# Micromouse_controller_v009.net
KiCad netlist of a schematic drawn in EAGLE
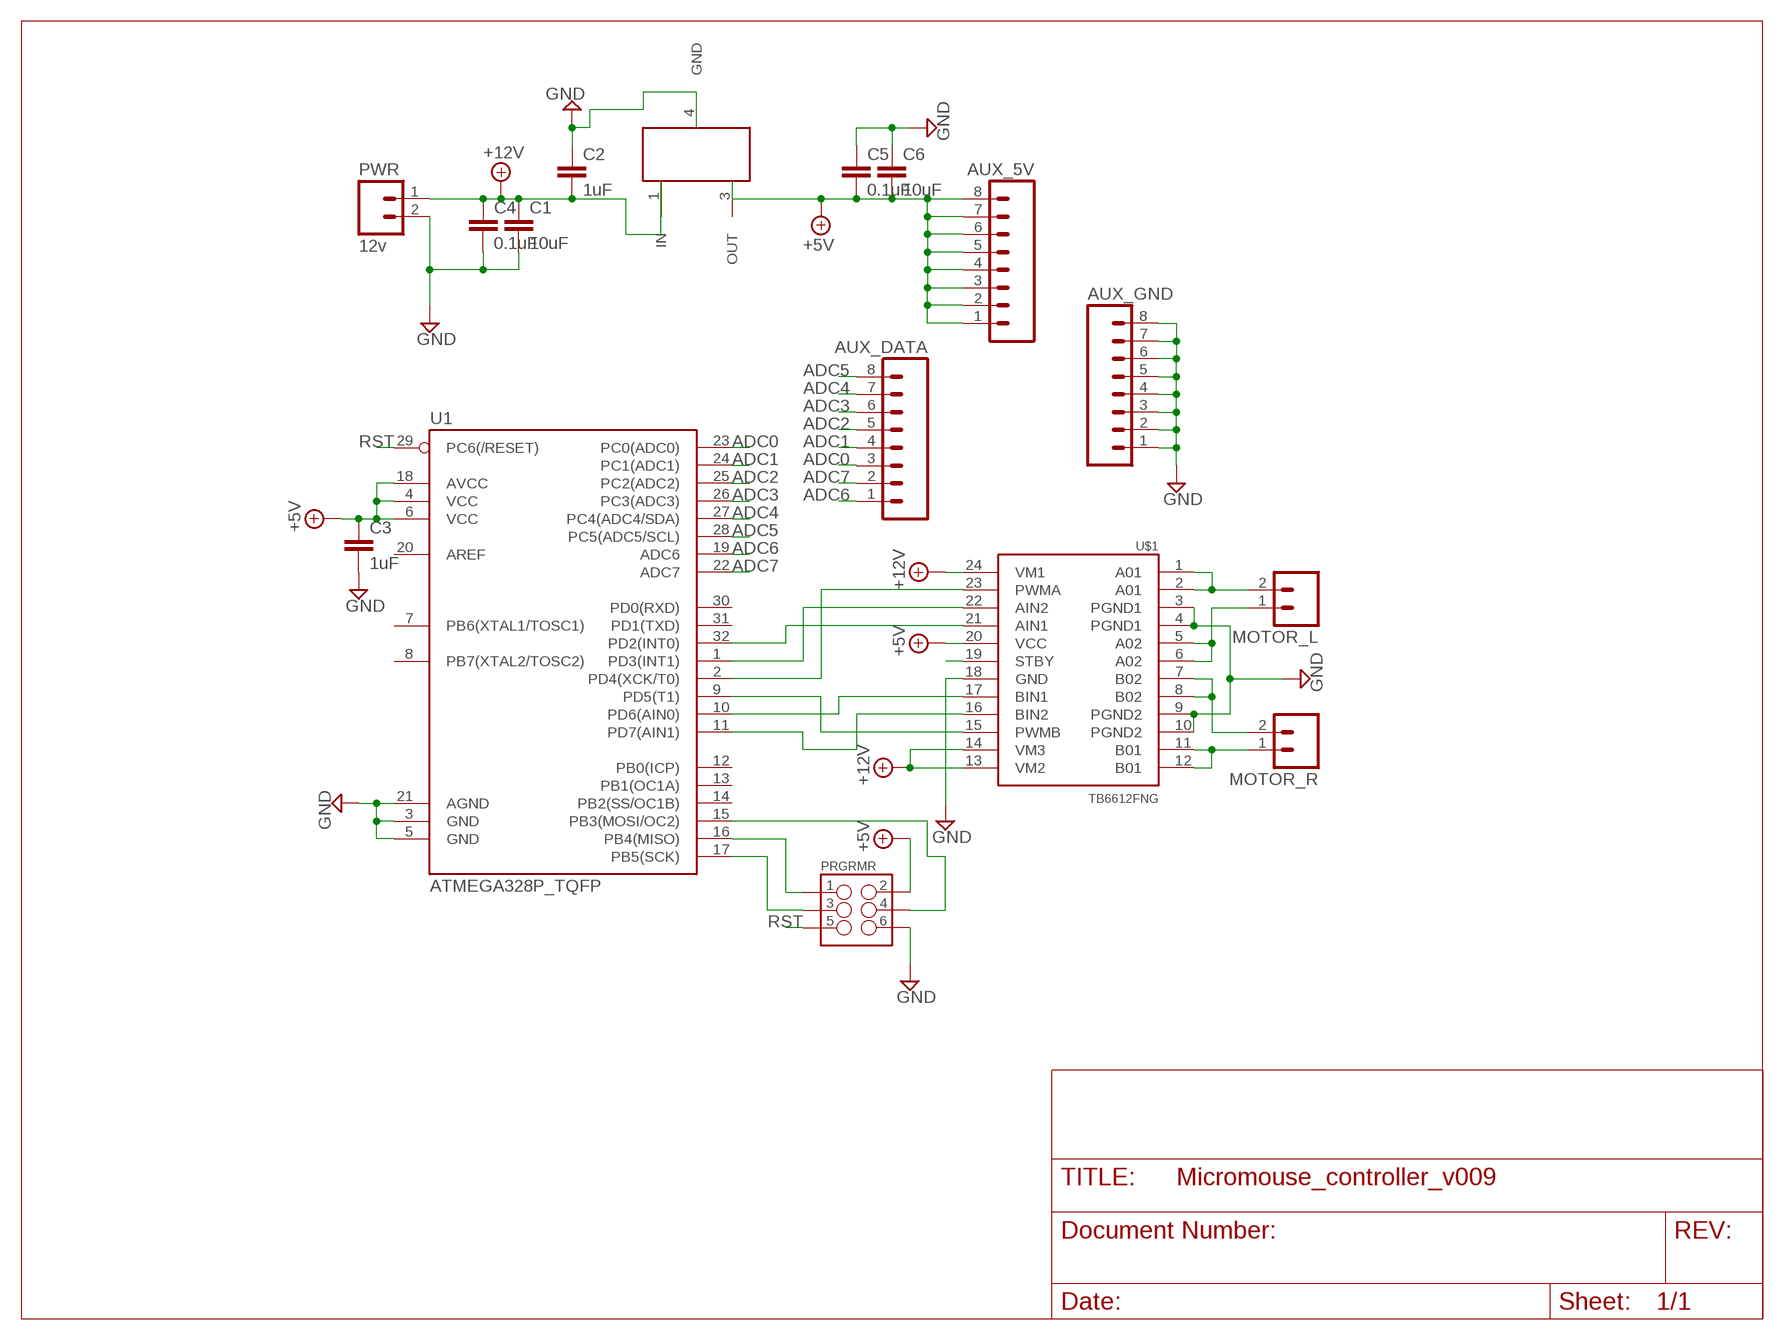
[diagram p0: schematic, sheet 1]

(export (version "E")
  (design (tool "Eeschema 10.0.6"))
  (components
    (comp (ref "AUX_5V")
      (value "M08SMD-STRAIGHT-ALT-FEMALE")
      (footprint "eagle-import:1X08_SMD_ALT")
      (libsource (lib "eagle-import") (part "M08SMD-STRAIGHT-ALT-FEMALE"))
    )
    (comp (ref "AUX_DATA")
      (value "M08SMD-STRAIGHT-ALT-FEMALE")
      (footprint "eagle-import:1X08_SMD_ALT")
      (libsource (lib "eagle-import") (part "M08SMD-STRAIGHT-ALT-FEMALE"))
    )
    (comp (ref "AUX_GND")
      (value "M08SMD-STRAIGHT-ALT-FEMALE")
      (footprint "eagle-import:1X08_SMD_ALT")
      (libsource (lib "eagle-import") (part "M08SMD-STRAIGHT-ALT-FEMALE"))
    )
    (comp (ref "C1")
      (value "10uF")
      (footprint "eagle-import:GRM43D")
      (libsource (lib "eagle-import") (part "CAPSMD"))
    )
    (comp (ref "C2")
      (value "1uF")
      (footprint "eagle-import:GRM43D")
      (libsource (lib "eagle-import") (part "CAPSMD"))
    )
    (comp (ref "C3")
      (value "1uF")
      (footprint "eagle-import:GRM43D")
      (libsource (lib "eagle-import") (part "CAPSMD"))
    )
    (comp (ref "C4")
      (value "0.1uF")
      (footprint "eagle-import:GRM43D")
      (libsource (lib "eagle-import") (part "CAPSMD"))
    )
    (comp (ref "C5")
      (value "0.1uF")
      (footprint "eagle-import:GRM43D")
      (libsource (lib "eagle-import") (part "CAPSMD"))
    )
    (comp (ref "C6")
      (value "10uF")
      (footprint "eagle-import:GRM43D")
      (libsource (lib "eagle-import") (part "CAPSMD"))
    )
    (comp (ref "IC2")
      (value "TA4805BF")
      (footprint "eagle-import:DPAK")
      (libsource (lib "eagle-import") (part "TA4805BF"))
    )
    (comp (ref "MOTOR_L")
      (value "M02-JST-2MM-SMT")
      (footprint "eagle-import:JST-2-SMD")
      (libsource (lib "eagle-import") (part "M02-JST-2MM-SMT"))
    )
    (comp (ref "MOTOR_R")
      (value "M02-JST-2MM-SMT")
      (footprint "eagle-import:JST-2-SMD")
      (libsource (lib "eagle-import") (part "M02-JST-2MM-SMT"))
    )
    (comp (ref "PRGRMR")
      (value "M03X2FEMALE_SMD")
      (footprint "eagle-import:2X3_SMD")
      (libsource (lib "eagle-import") (part "M03X2FEMALE_SMD"))
    )
    (comp (ref "PWR")
      (value "12v")
      (footprint "eagle-import:JST-2-SMD")
      (libsource (lib "eagle-import") (part "M02-JST-2MM-SMT"))
    )
    (comp (ref "U$1")
      (value "TB6612FNG")
      (footprint "eagle-import:SSOP24")
      (libsource (lib "eagle-import") (part "TB6612FNG"))
    )
    (comp (ref "U1")
      (value "ATMEGA328P_TQFP")
      (footprint "eagle-import:TQFP32-08")
      (libsource (lib "eagle-import") (part "ATMEGA328P_TQFP"))
    )
  )
  (nets
    (net (code "1") (name "+5V") (class "Default")
      (node (ref "AUX_5V") (pin "1") (pinfunction "1_1") (pintype "passive"))
      (node (ref "AUX_5V") (pin "2") (pinfunction "2_2") (pintype "passive"))
      (node (ref "AUX_5V") (pin "3") (pinfunction "3_3") (pintype "passive"))
      (node (ref "AUX_5V") (pin "4") (pinfunction "4_4") (pintype "passive"))
      (node (ref "AUX_5V") (pin "5") (pinfunction "5_5") (pintype "passive"))
      (node (ref "AUX_5V") (pin "6") (pinfunction "6_6") (pintype "passive"))
      (node (ref "AUX_5V") (pin "7") (pinfunction "7_7") (pintype "passive"))
      (node (ref "AUX_5V") (pin "8") (pinfunction "8_8") (pintype "passive"))
      (node (ref "C3") (pin "A") (pinfunction "1_A") (pintype "passive"))
      (node (ref "C5") (pin "C") (pinfunction "2_C") (pintype "passive"))
      (node (ref "C6") (pin "C") (pinfunction "2_C") (pintype "passive"))
      (node (ref "IC2") (pin "3") (pinfunction "OUT_3") (pintype "bidirectional"))
      (node (ref "PRGRMR") (pin "2") (pinfunction "2_2") (pintype "bidirectional"))
      (node (ref "U$1") (pin "20") (pinfunction "VCC_20") (pintype "bidirectional"))
      (node (ref "U1") (pin "18") (pinfunction "AVCC_18") (pintype "bidirectional"))
      (node (ref "U1") (pin "4") (pinfunction "VCC_4") (pintype "bidirectional"))
      (node (ref "U1") (pin "6") (pinfunction "VCC_6") (pintype "bidirectional"))
    )
    (net (code "2") (name "+12V") (class "Default")
      (node (ref "C1") (pin "A") (pinfunction "1_A") (pintype "passive"))
      (node (ref "C2") (pin "C") (pinfunction "2_C") (pintype "passive"))
      (node (ref "C4") (pin "A") (pinfunction "1_A") (pintype "passive"))
      (node (ref "IC2") (pin "1") (pinfunction "IN_1") (pintype "bidirectional"))
      (node (ref "PWR") (pin "1") (pinfunction "2_1") (pintype "passive"))
      (node (ref "U$1") (pin "13") (pinfunction "VM2_13") (pintype "bidirectional"))
      (node (ref "U$1") (pin "14") (pinfunction "VM3_14") (pintype "bidirectional"))
      (node (ref "U$1") (pin "24") (pinfunction "VM1_24") (pintype "bidirectional"))
    )
    (net (code "3") (name "/ADC0") (class "Default")
      (node (ref "AUX_DATA") (pin "3") (pinfunction "3_3") (pintype "passive"))
      (node (ref "U1") (pin "23") (pinfunction "PC0(ADC0)_23") (pintype "bidirectional"))
    )
    (net (code "4") (name "/ADC1") (class "Default")
      (node (ref "AUX_DATA") (pin "4") (pinfunction "4_4") (pintype "passive"))
      (node (ref "U1") (pin "24") (pinfunction "PC1(ADC1)_24") (pintype "bidirectional"))
    )
    (net (code "5") (name "/ADC2") (class "Default")
      (node (ref "AUX_DATA") (pin "5") (pinfunction "5_5") (pintype "passive"))
      (node (ref "U1") (pin "25") (pinfunction "PC2(ADC2)_25") (pintype "bidirectional"))
    )
    (net (code "6") (name "/ADC3") (class "Default")
      (node (ref "AUX_DATA") (pin "6") (pinfunction "6_6") (pintype "passive"))
      (node (ref "U1") (pin "26") (pinfunction "PC3(ADC3)_26") (pintype "bidirectional"))
    )
    (net (code "7") (name "/ADC4") (class "Default")
      (node (ref "AUX_DATA") (pin "7") (pinfunction "7_7") (pintype "passive"))
      (node (ref "U1") (pin "27") (pinfunction "PC4(ADC4/SDA)_27") (pintype "bidirectional"))
    )
    (net (code "8") (name "/ADC5") (class "Default")
      (node (ref "AUX_DATA") (pin "8") (pinfunction "8_8") (pintype "passive"))
      (node (ref "U1") (pin "28") (pinfunction "PC5(ADC5/SCL)_28") (pintype "bidirectional"))
    )
    (net (code "9") (name "/ADC6") (class "Default")
      (node (ref "AUX_DATA") (pin "1") (pinfunction "1_1") (pintype "passive"))
      (node (ref "U1") (pin "19") (pinfunction "ADC6_19") (pintype "bidirectional"))
    )
    (net (code "10") (name "/ADC7") (class "Default")
      (node (ref "AUX_DATA") (pin "2") (pinfunction "2_2") (pintype "passive"))
      (node (ref "U1") (pin "22") (pinfunction "ADC7_22") (pintype "bidirectional"))
    )
    (net (code "11") (name "/RST") (class "Default")
      (node (ref "PRGRMR") (pin "5") (pinfunction "5_5") (pintype "bidirectional"))
      (node (ref "U1") (pin "29") (pinfunction "PC6(/RESET)_29") (pintype "bidirectional"))
    )
    (net (code "12") (name "GND") (class "Default")
      (node (ref "AUX_GND") (pin "1") (pinfunction "1_1") (pintype "passive"))
      (node (ref "AUX_GND") (pin "2") (pinfunction "2_2") (pintype "passive"))
      (node (ref "AUX_GND") (pin "3") (pinfunction "3_3") (pintype "passive"))
      (node (ref "AUX_GND") (pin "4") (pinfunction "4_4") (pintype "passive"))
      (node (ref "AUX_GND") (pin "5") (pinfunction "5_5") (pintype "passive"))
      (node (ref "AUX_GND") (pin "6") (pinfunction "6_6") (pintype "passive"))
      (node (ref "AUX_GND") (pin "7") (pinfunction "7_7") (pintype "passive"))
      (node (ref "AUX_GND") (pin "8") (pinfunction "8_8") (pintype "passive"))
      (node (ref "C1") (pin "C") (pinfunction "2_C") (pintype "passive"))
      (node (ref "C2") (pin "A") (pinfunction "1_A") (pintype "passive"))
      (node (ref "C3") (pin "C") (pinfunction "2_C") (pintype "passive"))
      (node (ref "C4") (pin "C") (pinfunction "2_C") (pintype "passive"))
      (node (ref "C5") (pin "A") (pinfunction "1_A") (pintype "passive"))
      (node (ref "C6") (pin "A") (pinfunction "1_A") (pintype "passive"))
      (node (ref "IC2") (pin "4") (pinfunction "GND_4") (pintype "bidirectional"))
      (node (ref "PRGRMR") (pin "6") (pinfunction "6_6") (pintype "bidirectional"))
      (node (ref "PWR") (pin "2") (pinfunction "1_2") (pintype "passive"))
      (node (ref "U$1") (pin "10") (pinfunction "PGND2_10") (pintype "bidirectional"))
      (node (ref "U$1") (pin "18") (pinfunction "GND_18") (pintype "bidirectional"))
      (node (ref "U$1") (pin "3") (pinfunction "PGND1_3") (pintype "bidirectional"))
      (node (ref "U$1") (pin "4") (pinfunction "PGND1_4") (pintype "bidirectional"))
      (node (ref "U$1") (pin "9") (pinfunction "PGND2_9") (pintype "bidirectional"))
      (node (ref "U1") (pin "21") (pinfunction "AGND_21") (pintype "bidirectional"))
      (node (ref "U1") (pin "3") (pinfunction "GND_3") (pintype "bidirectional"))
      (node (ref "U1") (pin "5") (pinfunction "GND_5") (pintype "bidirectional"))
    )
    (net (code "13") (name "Net-(MOTOR_L-1)") (class "Default")
      (node (ref "MOTOR_L") (pin "2") (pinfunction "1_2") (pintype "passive"))
      (node (ref "U$1") (pin "1") (pinfunction "A01_1") (pintype "bidirectional"))
      (node (ref "U$1") (pin "2") (pinfunction "A01_2") (pintype "bidirectional"))
    )
    (net (code "14") (name "Net-(MOTOR_L-2)") (class "Default")
      (node (ref "MOTOR_L") (pin "1") (pinfunction "2_1") (pintype "passive"))
      (node (ref "U$1") (pin "5") (pinfunction "A02_5") (pintype "bidirectional"))
      (node (ref "U$1") (pin "6") (pinfunction "A02_6") (pintype "bidirectional"))
    )
    (net (code "15") (name "Net-(MOTOR_R-1)") (class "Default")
      (node (ref "MOTOR_R") (pin "2") (pinfunction "1_2") (pintype "passive"))
      (node (ref "U$1") (pin "7") (pinfunction "B02_7") (pintype "bidirectional"))
      (node (ref "U$1") (pin "8") (pinfunction "B02_8") (pintype "bidirectional"))
    )
    (net (code "16") (name "Net-(MOTOR_R-2)") (class "Default")
      (node (ref "MOTOR_R") (pin "1") (pinfunction "2_1") (pintype "passive"))
      (node (ref "U$1") (pin "11") (pinfunction "B01_11") (pintype "bidirectional"))
      (node (ref "U$1") (pin "12") (pinfunction "B01_12") (pintype "bidirectional"))
    )
    (net (code "17") (name "Net-(U$1-AIN1)") (class "Default")
      (node (ref "U$1") (pin "21") (pinfunction "AIN1_21") (pintype "bidirectional"))
      (node (ref "U1") (pin "32") (pinfunction "PD2(INT0)_32") (pintype "bidirectional"))
    )
    (net (code "18") (name "Net-(U$1-AIN2)") (class "Default")
      (node (ref "U$1") (pin "22") (pinfunction "AIN2_22") (pintype "bidirectional"))
      (node (ref "U1") (pin "1") (pinfunction "PD3(INT1)_1") (pintype "bidirectional"))
    )
    (net (code "19") (name "Net-(U$1-BIN1)") (class "Default")
      (node (ref "U$1") (pin "17") (pinfunction "BIN1_17") (pintype "bidirectional"))
      (node (ref "U1") (pin "10") (pinfunction "PD6(AIN0)_10") (pintype "bidirectional"))
    )
    (net (code "20") (name "Net-(U$1-BIN2)") (class "Default")
      (node (ref "U$1") (pin "16") (pinfunction "BIN2_16") (pintype "bidirectional"))
      (node (ref "U1") (pin "11") (pinfunction "PD7(AIN1)_11") (pintype "bidirectional"))
    )
    (net (code "21") (name "Net-(U$1-PWMA)") (class "Default")
      (node (ref "U$1") (pin "23") (pinfunction "PWMA_23") (pintype "bidirectional"))
      (node (ref "U1") (pin "2") (pinfunction "PD4(XCK/T0)_2") (pintype "bidirectional"))
    )
    (net (code "22") (name "Net-(U$1-PWMB)") (class "Default")
      (node (ref "U$1") (pin "15") (pinfunction "PWMB_15") (pintype "bidirectional"))
      (node (ref "U1") (pin "9") (pinfunction "PD5(T1)_9") (pintype "bidirectional"))
    )
    (net (code "23") (name "Net-(U1-PB3(MOSI{slash}OC2))") (class "Default")
      (node (ref "PRGRMR") (pin "4") (pinfunction "4_4") (pintype "bidirectional"))
      (node (ref "U1") (pin "15") (pinfunction "PB3(MOSI/OC2)_15") (pintype "bidirectional"))
    )
    (net (code "24") (name "Net-(U1-PB4(MISO))") (class "Default")
      (node (ref "PRGRMR") (pin "1") (pinfunction "1_1") (pintype "bidirectional"))
      (node (ref "U1") (pin "16") (pinfunction "PB4(MISO)_16") (pintype "bidirectional"))
    )
    (net (code "25") (name "Net-(U1-PB5(SCK))") (class "Default")
      (node (ref "PRGRMR") (pin "3") (pinfunction "3_3") (pintype "bidirectional"))
      (node (ref "U1") (pin "17") (pinfunction "PB5(SCK)_17") (pintype "bidirectional"))
    )
    (net (code "26") (name "unconnected-(U$1-STBY-Pad19)") (class "Default")
      (node (ref "U$1") (pin "19") (pinfunction "STBY_19") (pintype "bidirectional"))
    )
    (net (code "27") (name "unconnected-(U1-AREF-Pad20)") (class "Default")
      (node (ref "U1") (pin "20") (pinfunction "AREF_20") (pintype "bidirectional"))
    )
    (net (code "28") (name "unconnected-(U1-PB0(ICP)-Pad12)") (class "Default")
      (node (ref "U1") (pin "12") (pinfunction "PB0(ICP)_12") (pintype "bidirectional"))
    )
    (net (code "29") (name "unconnected-(U1-PB1(OC1A)-Pad13)") (class "Default")
      (node (ref "U1") (pin "13") (pinfunction "PB1(OC1A)_13") (pintype "bidirectional"))
    )
    (net (code "30") (name "unconnected-(U1-PB2(SS{slash}OC1B)-Pad14)") (class "Default")
      (node (ref "U1") (pin "14") (pinfunction "PB2(SS/OC1B)_14") (pintype "bidirectional"))
    )
    (net (code "31") (name "unconnected-(U1-PB6(XTAL1{slash}TOSC1)-Pad7)") (class "Default")
      (node (ref "U1") (pin "7") (pinfunction "PB6(XTAL1/TOSC1)_7") (pintype "bidirectional"))
    )
    (net (code "32") (name "unconnected-(U1-PB7(XTAL2{slash}TOSC2)-Pad8)") (class "Default")
      (node (ref "U1") (pin "8") (pinfunction "PB7(XTAL2/TOSC2)_8") (pintype "bidirectional"))
    )
    (net (code "33") (name "unconnected-(U1-PD0(RXD)-Pad30)") (class "Default")
      (node (ref "U1") (pin "30") (pinfunction "PD0(RXD)_30") (pintype "bidirectional"))
    )
    (net (code "34") (name "unconnected-(U1-PD1(TXD)-Pad31)") (class "Default")
      (node (ref "U1") (pin "31") (pinfunction "PD1(TXD)_31") (pintype "bidirectional"))
    )
  )
)
